# lcd13264-shield.net
KiCad netlist of a schematic drawn in EAGLE
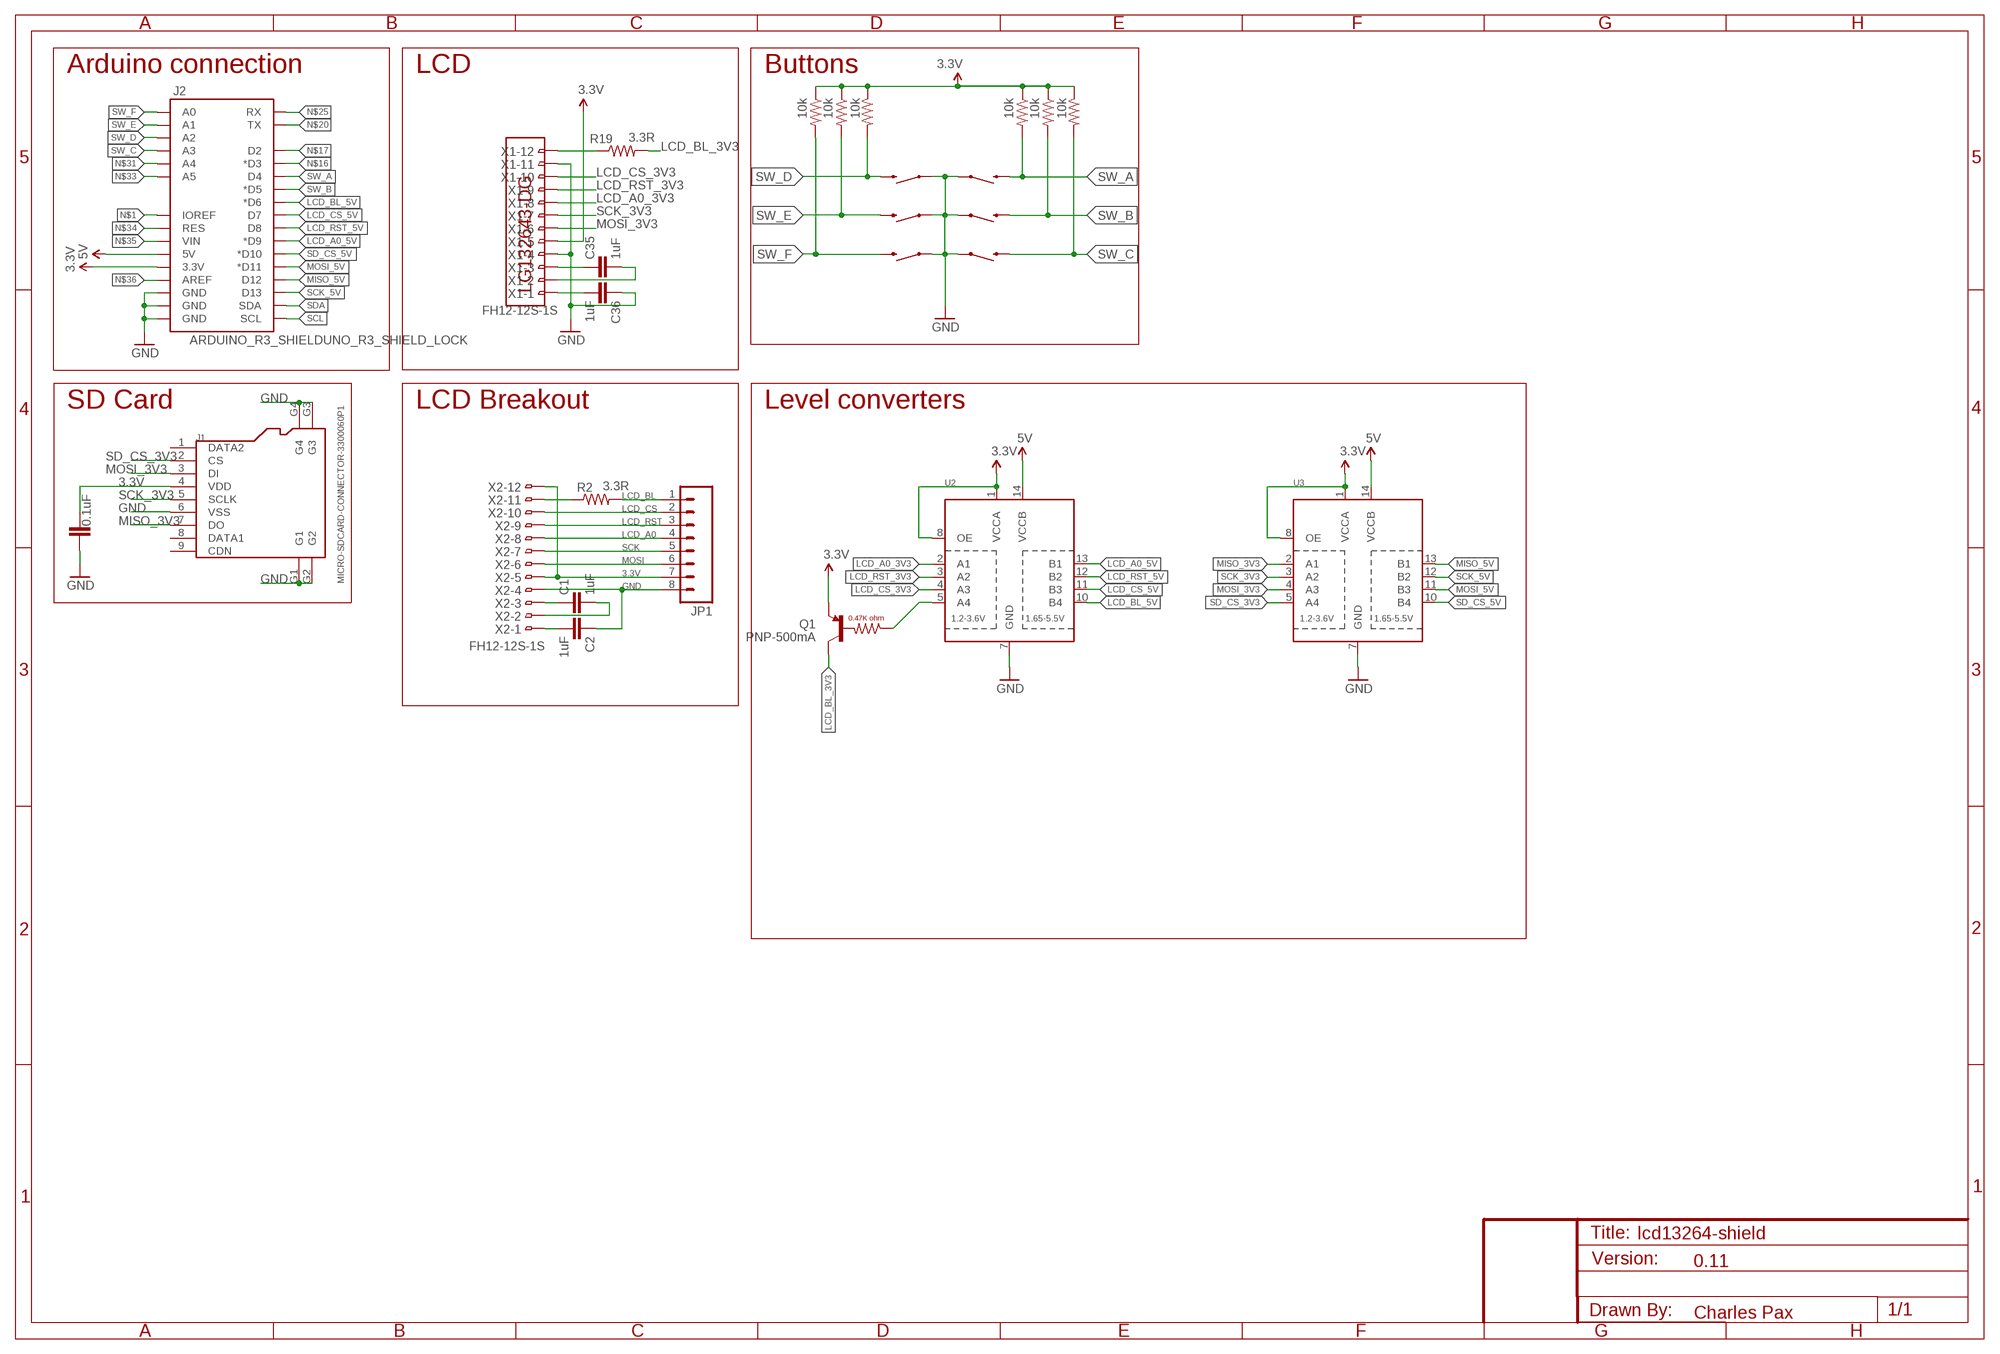
[diagram p0: schematic, sheet 1]

(export (version "E")
  (design (tool "Eeschema 10.0.6"))
  (components
    (comp (ref "C1")
      (value "1uF")
      (footprint "eagle-import:SPARKFUN-CAPACITORS_0603-CAP")
      (fields (field (name "MPN") "LMK107B7105KA-T"))
      (libsource (lib "eagle-import") (part "SPARKFUN-CAPACITORS_CAP0603-CAP"))
    )
    (comp (ref "C2")
      (value "1uF")
      (footprint "eagle-import:SPARKFUN-CAPACITORS_0603-CAP")
      (fields (field (name "MPN") "LMK107B7105KA-T"))
      (libsource (lib "eagle-import") (part "SPARKFUN-CAPACITORS_CAP0603-CAP"))
    )
    (comp (ref "C21")
      (value "0.1uF")
      (footprint "eagle-import:SPARKFUN-CAPACITORS_0603-CAP")
      (fields (field (name "MPN") "CL10B104KO8NNNC"))
      (libsource (lib "eagle-import") (part "SPARKFUN-CAPACITORS_CAP0603-CAP"))
    )
    (comp (ref "C35")
      (value "1uF")
      (footprint "eagle-import:SPARKFUN-CAPACITORS_0603-CAP")
      (fields (field (name "MPN") "LMK107B7105KA-T"))
      (libsource (lib "eagle-import") (part "SPARKFUN-CAPACITORS_CAP0603-CAP"))
    )
    (comp (ref "C36")
      (value "1uF")
      (footprint "eagle-import:SPARKFUN-CAPACITORS_0603-CAP")
      (fields (field (name "MPN") "LMK107B7105KA-T"))
      (libsource (lib "eagle-import") (part "SPARKFUN-CAPACITORS_CAP0603-CAP"))
    )
    (comp (ref "J1")
      (value "MICRO-SDCARD-CONNECTOR-3300060P1")
      (footprint "eagle-import:9P-SMD-W-RING")
      (libsource (lib "eagle-import") (part "MICRO-SDCARD-CONNECTOR-3300060P1"))
    )
    (comp (ref "J2")
      (value "ARDUINO_R3_SHIELDUNO_R3_SHIELD_LOCK")
      (footprint "eagle-import:UNO_R3_SHIELD_LOCK")
      (libsource (lib "eagle-import") (part "ARDUINO_R3_SHIELDUNO_R3_SHIELD_LOCK"))
    )
    (comp (ref "JP1")
      (value "M08")
      (footprint "eagle-import:1X08_ROUND")
      (libsource (lib "eagle-import") (part "M08"))
    )
    (comp (ref "Q1")
      (value "PNP-500mA")
      (footprint "eagle-import:SOT23-3")
      (libsource (lib "eagle-import") (part "TRANSISTOR-PNP-DDTB142TC"))
    )
    (comp (ref "R1")
      (value "10k")
      (footprint "eagle-import:SPARKFUN-RESISTORS_0603-RES")
      (fields (field (name "MPN") "RC1608J103CS"))
      (libsource (lib "eagle-import") (part "SPARKFUN-RESISTORS_RESISTOR0603-RES"))
    )
    (comp (ref "R2")
      (value "3.3R")
      (footprint "eagle-import:SPARKFUN-RESISTORS_0603-RES")
      (libsource (lib "eagle-import") (part "SPARKFUN-RESISTORS_RESISTOR0603-RES"))
    )
    (comp (ref "R8")
      (value "10k")
      (footprint "eagle-import:SPARKFUN-RESISTORS_0603-RES")
      (fields (field (name "MPN") "RC1608J103CS"))
      (libsource (lib "eagle-import") (part "SPARKFUN-RESISTORS_RESISTOR0603-RES"))
    )
    (comp (ref "R11")
      (value "10k")
      (footprint "eagle-import:SPARKFUN-RESISTORS_0603-RES")
      (fields (field (name "MPN") "RC1608J103CS"))
      (libsource (lib "eagle-import") (part "SPARKFUN-RESISTORS_RESISTOR0603-RES"))
    )
    (comp (ref "R12")
      (value "10k")
      (footprint "eagle-import:SPARKFUN-RESISTORS_0603-RES")
      (fields (field (name "MPN") "RC1608J103CS"))
      (libsource (lib "eagle-import") (part "SPARKFUN-RESISTORS_RESISTOR0603-RES"))
    )
    (comp (ref "R15")
      (value "10k")
      (footprint "eagle-import:SPARKFUN-RESISTORS_0603-RES")
      (fields (field (name "MPN") "RC1608J103CS"))
      (libsource (lib "eagle-import") (part "SPARKFUN-RESISTORS_RESISTOR0603-RES"))
    )
    (comp (ref "R16")
      (value "10k")
      (footprint "eagle-import:SPARKFUN-RESISTORS_0603-RES")
      (fields (field (name "MPN") "RC1608J103CS"))
      (libsource (lib "eagle-import") (part "SPARKFUN-RESISTORS_RESISTOR0603-RES"))
    )
    (comp (ref "R19")
      (value "3.3R")
      (footprint "eagle-import:SPARKFUN-RESISTORS_0603-RES")
      (libsource (lib "eagle-import") (part "SPARKFUN-RESISTORS_RESISTOR0603-RES"))
    )
    (comp (ref "S1")
      (value "SWITCH-MOMENTARY-2SMD")
      (footprint "eagle-import:TACTILE_SWITCH_SMD")
      (libsource (lib "eagle-import") (part "SWITCH-MOMENTARY-2SMD"))
    )
    (comp (ref "S2")
      (value "SWITCH-MOMENTARY-2SMD")
      (footprint "eagle-import:TACTILE_SWITCH_SMD")
      (libsource (lib "eagle-import") (part "SWITCH-MOMENTARY-2SMD"))
    )
    (comp (ref "S3")
      (value "SWITCH-MOMENTARY-2SMD")
      (footprint "eagle-import:TACTILE_SWITCH_SMD")
      (libsource (lib "eagle-import") (part "SWITCH-MOMENTARY-2SMD"))
    )
    (comp (ref "S4")
      (value "SWITCH-MOMENTARY-2SMD")
      (footprint "eagle-import:TACTILE_SWITCH_SMD")
      (libsource (lib "eagle-import") (part "SWITCH-MOMENTARY-2SMD"))
    )
    (comp (ref "S5")
      (value "SWITCH-MOMENTARY-2SMD")
      (footprint "eagle-import:TACTILE_SWITCH_SMD")
      (libsource (lib "eagle-import") (part "SWITCH-MOMENTARY-2SMD"))
    )
    (comp (ref "S6")
      (value "SWITCH-MOMENTARY-2SMD")
      (footprint "eagle-import:TACTILE_SWITCH_SMD")
      (libsource (lib "eagle-import") (part "SWITCH-MOMENTARY-2SMD"))
    )
    (comp (ref "U$5")
      (value "LG132643-DG")
      (footprint "eagle-import:LG132643-DG")
      (fields (field (name "MPN") "LG132643-DW"))
      (libsource (lib "eagle-import") (part "LG132643-DG"))
    )
    (comp (ref "U2")
      (value "TXB0104PWRSOIC14")
      (footprint "eagle-import:SO14")
      (libsource (lib "eagle-import") (part "TXB0104PWRSOIC14"))
    )
    (comp (ref "U3")
      (value "TXB0104PWRSOIC14")
      (footprint "eagle-import:SO14")
      (libsource (lib "eagle-import") (part "TXB0104PWRSOIC14"))
    )
    (comp (ref "X1")
      (value "FH12-12S-1S")
      (footprint "eagle-import:FH12-12S-1SH")
      (libsource (lib "eagle-import") (part "FH12-12S-1S"))
    )
    (comp (ref "X2")
      (value "FH12-12S-1S")
      (footprint "eagle-import:FH12-12S-1SH")
      (libsource (lib "eagle-import") (part "FH12-12S-1S"))
    )
  )
  (nets
    (net (code "1") (name "3.3V") (class "Default")
      (node (ref "C21") (pin "2") (pinfunction "2_2") (pintype "passive"))
      (node (ref "J1") (pin "4") (pinfunction "VDD_4") (pintype "bidirectional"))
      (node (ref "J2") (pin "3.3V") (pinfunction "3.3V_3.3V") (pintype "bidirectional"))
      (node (ref "Q1") (pin "2") (pinfunction "E_2") (pintype "passive"))
      (node (ref "R1") (pin "1") (pinfunction "1_1") (pintype "passive"))
      (node (ref "R11") (pin "1") (pinfunction "1_1") (pintype "passive"))
      (node (ref "R12") (pin "1") (pinfunction "1_1") (pintype "passive"))
      (node (ref "R15") (pin "1") (pinfunction "1_1") (pintype "passive"))
      (node (ref "R16") (pin "1") (pinfunction "1_1") (pintype "passive"))
      (node (ref "R8") (pin "1") (pinfunction "1_1") (pintype "passive"))
      (node (ref "U2") (pin "1") (pinfunction "VCCA_1") (pintype "bidirectional"))
      (node (ref "U2") (pin "8") (pinfunction "OE_8") (pintype "bidirectional"))
      (node (ref "U3") (pin "1") (pinfunction "VCCA_1") (pintype "bidirectional"))
      (node (ref "U3") (pin "8") (pinfunction "OE_8") (pintype "bidirectional"))
      (node (ref "X1") (pin "5") (pinfunction "1_5") (pintype "passive"))
    )
    (net (code "2") (name "5V") (class "Default")
      (node (ref "J2") (pin "5V") (pinfunction "5V_5V") (pintype "bidirectional"))
      (node (ref "U2") (pin "14") (pinfunction "VCCB_14") (pintype "bidirectional"))
      (node (ref "U3") (pin "14") (pinfunction "VCCB_14") (pintype "bidirectional"))
    )
    (net (code "3") (name "GND") (class "Default")
      (node (ref "C21") (pin "1") (pinfunction "1_1") (pintype "passive"))
      (node (ref "C36") (pin "1") (pinfunction "1_1") (pintype "passive"))
      (node (ref "J1") (pin "6") (pinfunction "VSS_6") (pintype "bidirectional"))
      (node (ref "J1") (pin "G1") (pinfunction "G1_G1") (pintype "bidirectional"))
      (node (ref "J1") (pin "G2") (pinfunction "G2_G2") (pintype "bidirectional"))
      (node (ref "J1") (pin "G3") (pinfunction "G3_G3") (pintype "bidirectional"))
      (node (ref "J1") (pin "G4") (pinfunction "G4_G4") (pintype "bidirectional"))
      (node (ref "J2") (pin "GND@0") (pinfunction "GND_GND@0") (pintype "bidirectional"))
      (node (ref "J2") (pin "GND@1") (pinfunction "GND_GND@1") (pintype "bidirectional"))
      (node (ref "J2") (pin "GND@2") (pinfunction "GND_GND@2") (pintype "bidirectional"))
      (node (ref "S1") (pin "1") (pinfunction "1_1") (pintype "passive"))
      (node (ref "S2") (pin "1") (pinfunction "1_1") (pintype "passive"))
      (node (ref "S3") (pin "1") (pinfunction "1_1") (pintype "passive"))
      (node (ref "S4") (pin "1") (pinfunction "1_1") (pintype "passive"))
      (node (ref "S5") (pin "1") (pinfunction "1_1") (pintype "passive"))
      (node (ref "S6") (pin "1") (pinfunction "1_1") (pintype "passive"))
      (node (ref "U2") (pin "7") (pinfunction "GND_7") (pintype "bidirectional"))
      (node (ref "U3") (pin "7") (pinfunction "GND_7") (pintype "bidirectional"))
      (node (ref "X1") (pin "11") (pinfunction "1_11") (pintype "passive"))
      (node (ref "X1") (pin "4") (pinfunction "1_4") (pintype "passive"))
    )
    (net (code "4") (name "LCD_A0_3V3") (class "Default")
      (node (ref "U2") (pin "2") (pinfunction "A1_2") (pintype "bidirectional"))
      (node (ref "X1") (pin "8") (pinfunction "1_8") (pintype "passive"))
    )
    (net (code "5") (name "LCD_A0_5V") (class "Default")
      (node (ref "J2") (pin "D9") (pinfunction "*D9_D9") (pintype "bidirectional"))
      (node (ref "U2") (pin "13") (pinfunction "B1_13") (pintype "bidirectional"))
    )
    (net (code "6") (name "LCD_BL_3V3") (class "Default")
      (node (ref "Q1") (pin "3") (pinfunction "C_3") (pintype "passive"))
      (node (ref "R19") (pin "2") (pinfunction "2_2") (pintype "passive"))
    )
    (net (code "7") (name "LCD_BL_5V") (class "Default")
      (node (ref "J2") (pin "D6") (pinfunction "*D6_D6") (pintype "bidirectional"))
      (node (ref "U2") (pin "10") (pinfunction "B4_10") (pintype "bidirectional"))
    )
    (net (code "8") (name "LCD_CS_3V3") (class "Default")
      (node (ref "U2") (pin "4") (pinfunction "A3_4") (pintype "bidirectional"))
      (node (ref "X1") (pin "10") (pinfunction "1_10") (pintype "passive"))
    )
    (net (code "9") (name "LCD_CS_5V") (class "Default")
      (node (ref "J2") (pin "D7") (pinfunction "D7_D7") (pintype "bidirectional"))
      (node (ref "U2") (pin "11") (pinfunction "B3_11") (pintype "bidirectional"))
    )
    (net (code "10") (name "LCD_RST_3V3") (class "Default")
      (node (ref "U2") (pin "3") (pinfunction "A2_3") (pintype "bidirectional"))
      (node (ref "X1") (pin "9") (pinfunction "1_9") (pintype "passive"))
    )
    (net (code "11") (name "LCD_RST_5V") (class "Default")
      (node (ref "J2") (pin "D8") (pinfunction "D8_D8") (pintype "bidirectional"))
      (node (ref "U2") (pin "12") (pinfunction "B2_12") (pintype "bidirectional"))
    )
    (net (code "12") (name "MISO_3V3") (class "Default")
      (node (ref "J1") (pin "7") (pinfunction "DO_7") (pintype "bidirectional"))
      (node (ref "U3") (pin "2") (pinfunction "A1_2") (pintype "bidirectional"))
    )
    (net (code "13") (name "MISO_5V") (class "Default")
      (node (ref "J2") (pin "D12") (pinfunction "D12_D12") (pintype "bidirectional"))
      (node (ref "U3") (pin "13") (pinfunction "B1_13") (pintype "bidirectional"))
    )
    (net (code "14") (name "MOSI_3V3") (class "Default")
      (node (ref "J1") (pin "3") (pinfunction "DI_3") (pintype "bidirectional"))
      (node (ref "U3") (pin "4") (pinfunction "A3_4") (pintype "bidirectional"))
      (node (ref "X1") (pin "6") (pinfunction "1_6") (pintype "passive"))
    )
    (net (code "15") (name "MOSI_5V") (class "Default")
      (node (ref "J2") (pin "D11") (pinfunction "*D11_D11") (pintype "bidirectional"))
      (node (ref "U3") (pin "11") (pinfunction "B3_11") (pintype "bidirectional"))
    )
    (net (code "16") (name "N$1") (class "Default")
      (node (ref "J2") (pin "IOREF") (pinfunction "IOREF_IOREF") (pintype "bidirectional"))
    )
    (net (code "17") (name "N$16") (class "Default")
      (node (ref "J2") (pin "D3") (pinfunction "*D3_D3") (pintype "bidirectional"))
    )
    (net (code "18") (name "N$17") (class "Default")
      (node (ref "J2") (pin "D2") (pinfunction "D2_D2") (pintype "bidirectional"))
    )
    (net (code "19") (name "N$20") (class "Default")
      (node (ref "J2") (pin "TX") (pinfunction "TX_TX") (pintype "bidirectional"))
    )
    (net (code "20") (name "N$25") (class "Default")
      (node (ref "J2") (pin "RX") (pinfunction "RX_RX") (pintype "bidirectional"))
    )
    (net (code "21") (name "N$31") (class "Default")
      (node (ref "J2") (pin "A4") (pinfunction "A4_A4") (pintype "bidirectional"))
    )
    (net (code "22") (name "N$33") (class "Default")
      (node (ref "J2") (pin "A5") (pinfunction "A5_A5") (pintype "bidirectional"))
    )
    (net (code "23") (name "N$34") (class "Default")
      (node (ref "J2") (pin "RES") (pinfunction "RES_RES") (pintype "bidirectional"))
    )
    (net (code "24") (name "N$35") (class "Default")
      (node (ref "J2") (pin "VIN") (pinfunction "VIN_VIN") (pintype "bidirectional"))
    )
    (net (code "25") (name "N$36") (class "Default")
      (node (ref "J2") (pin "AREF") (pinfunction "AREF_AREF") (pintype "bidirectional"))
    )
    (net (code "26") (name "Net-(C2-Pad2)") (class "Default")
      (node (ref "C2") (pin "2") (pinfunction "2_2") (pintype "passive"))
      (node (ref "X2") (pin "1") (pinfunction "1_1") (pintype "passive"))
    )
    (net (code "27") (name "Net-(C36-Pad2)") (class "Default")
      (node (ref "C36") (pin "2") (pinfunction "2_2") (pintype "passive"))
      (node (ref "X1") (pin "1") (pinfunction "1_1") (pintype "passive"))
    )
    (net (code "28") (name "Net-(JP1-Pad1)") (class "Default")
      (node (ref "JP1") (pin "1") (pinfunction "1_1") (pintype "passive"))
      (node (ref "R2") (pin "2") (pinfunction "2_2") (pintype "passive"))
    )
    (net (code "29") (name "Net-(Q1-B)") (class "Default")
      (node (ref "Q1") (pin "1") (pinfunction "B_1") (pintype "passive"))
      (node (ref "U2") (pin "5") (pinfunction "A4_5") (pintype "bidirectional"))
    )
    (net (code "30") (name "Net-(X1D-1)") (class "Default")
      (node (ref "R19") (pin "1") (pinfunction "1_1") (pintype "passive"))
      (node (ref "X1") (pin "12") (pinfunction "1_12") (pintype "passive"))
    )
    (net (code "31") (name "Net-(X1E-1)") (class "Default")
      (node (ref "C35") (pin "2") (pinfunction "2_2") (pintype "passive"))
      (node (ref "X1") (pin "2") (pinfunction "1_2") (pintype "passive"))
    )
    (net (code "32") (name "Net-(X1F-1)") (class "Default")
      (node (ref "C35") (pin "1") (pinfunction "1_1") (pintype "passive"))
      (node (ref "X1") (pin "3") (pinfunction "1_3") (pintype "passive"))
    )
    (net (code "33") (name "Net-(X2B-1)") (class "Default")
      (node (ref "JP1") (pin "2") (pinfunction "2_2") (pintype "passive"))
      (node (ref "X2") (pin "10") (pinfunction "1_10") (pintype "passive"))
    )
    (net (code "34") (name "Net-(X2C-1)") (class "Default")
      (node (ref "R2") (pin "1") (pinfunction "1_1") (pintype "passive"))
      (node (ref "X2") (pin "11") (pinfunction "1_11") (pintype "passive"))
    )
    (net (code "35") (name "Net-(X2D-1)") (class "Default")
      (node (ref "JP1") (pin "7") (pinfunction "7_7") (pintype "passive"))
      (node (ref "X2") (pin "12") (pinfunction "1_12") (pintype "passive"))
      (node (ref "X2") (pin "5") (pinfunction "1_5") (pintype "passive"))
    )
    (net (code "36") (name "Net-(X2E-1)") (class "Default")
      (node (ref "C1") (pin "2") (pinfunction "2_2") (pintype "passive"))
      (node (ref "X2") (pin "2") (pinfunction "1_2") (pintype "passive"))
    )
    (net (code "37") (name "Net-(X2F-1)") (class "Default")
      (node (ref "C1") (pin "1") (pinfunction "1_1") (pintype "passive"))
      (node (ref "X2") (pin "3") (pinfunction "1_3") (pintype "passive"))
    )
    (net (code "38") (name "Net-(X2G-1)") (class "Default")
      (node (ref "C2") (pin "1") (pinfunction "1_1") (pintype "passive"))
      (node (ref "JP1") (pin "8") (pinfunction "8_8") (pintype "passive"))
      (node (ref "X2") (pin "4") (pinfunction "1_4") (pintype "passive"))
    )
    (net (code "39") (name "Net-(X2I-1)") (class "Default")
      (node (ref "JP1") (pin "6") (pinfunction "6_6") (pintype "passive"))
      (node (ref "X2") (pin "6") (pinfunction "1_6") (pintype "passive"))
    )
    (net (code "40") (name "Net-(X2J-1)") (class "Default")
      (node (ref "JP1") (pin "5") (pinfunction "5_5") (pintype "passive"))
      (node (ref "X2") (pin "7") (pinfunction "1_7") (pintype "passive"))
    )
    (net (code "41") (name "Net-(X2K-1)") (class "Default")
      (node (ref "JP1") (pin "4") (pinfunction "4_4") (pintype "passive"))
      (node (ref "X2") (pin "8") (pinfunction "1_8") (pintype "passive"))
    )
    (net (code "42") (name "Net-(X2L-1)") (class "Default")
      (node (ref "JP1") (pin "3") (pinfunction "3_3") (pintype "passive"))
      (node (ref "X2") (pin "9") (pinfunction "1_9") (pintype "passive"))
    )
    (net (code "43") (name "SCK_3V3") (class "Default")
      (node (ref "J1") (pin "5") (pinfunction "SCLK_5") (pintype "bidirectional"))
      (node (ref "U3") (pin "3") (pinfunction "A2_3") (pintype "bidirectional"))
      (node (ref "X1") (pin "7") (pinfunction "1_7") (pintype "passive"))
    )
    (net (code "44") (name "SCK_5V") (class "Default")
      (node (ref "J2") (pin "D13") (pinfunction "D13_D13") (pintype "bidirectional"))
      (node (ref "U3") (pin "12") (pinfunction "B2_12") (pintype "bidirectional"))
    )
    (net (code "45") (name "SCL") (class "Default")
      (node (ref "J2") (pin "SCL") (pinfunction "SCL_SCL") (pintype "bidirectional"))
    )
    (net (code "46") (name "SDA") (class "Default")
      (node (ref "J2") (pin "SDA") (pinfunction "SDA_SDA") (pintype "bidirectional"))
    )
    (net (code "47") (name "SD_CS_3V3") (class "Default")
      (node (ref "J1") (pin "2") (pinfunction "CS_2") (pintype "bidirectional"))
      (node (ref "U3") (pin "5") (pinfunction "A4_5") (pintype "bidirectional"))
    )
    (net (code "48") (name "SD_CS_5V") (class "Default")
      (node (ref "J2") (pin "D10") (pinfunction "*D10_D10") (pintype "bidirectional"))
      (node (ref "U3") (pin "10") (pinfunction "B4_10") (pintype "bidirectional"))
    )
    (net (code "49") (name "SW_A") (class "Default")
      (node (ref "J2") (pin "D4") (pinfunction "D4_D4") (pintype "bidirectional"))
      (node (ref "R8") (pin "2") (pinfunction "2_2") (pintype "passive"))
      (node (ref "S3") (pin "3") (pinfunction "2_3") (pintype "passive"))
    )
    (net (code "50") (name "SW_B") (class "Default")
      (node (ref "J2") (pin "D5") (pinfunction "*D5_D5") (pintype "bidirectional"))
      (node (ref "R11") (pin "2") (pinfunction "2_2") (pintype "passive"))
      (node (ref "S2") (pin "3") (pinfunction "2_3") (pintype "passive"))
    )
    (net (code "51") (name "SW_C") (class "Default")
      (node (ref "J2") (pin "A3") (pinfunction "A3_A3") (pintype "bidirectional"))
      (node (ref "R12") (pin "2") (pinfunction "2_2") (pintype "passive"))
      (node (ref "S1") (pin "3") (pinfunction "2_3") (pintype "passive"))
    )
    (net (code "52") (name "SW_D") (class "Default")
      (node (ref "J2") (pin "A2") (pinfunction "A2_A2") (pintype "bidirectional"))
      (node (ref "R15") (pin "2") (pinfunction "2_2") (pintype "passive"))
      (node (ref "S4") (pin "3") (pinfunction "2_3") (pintype "passive"))
    )
    (net (code "53") (name "SW_E") (class "Default")
      (node (ref "J2") (pin "A1") (pinfunction "A1_A1") (pintype "bidirectional"))
      (node (ref "R16") (pin "2") (pinfunction "2_2") (pintype "passive"))
      (node (ref "S5") (pin "3") (pinfunction "2_3") (pintype "passive"))
    )
    (net (code "54") (name "SW_F") (class "Default")
      (node (ref "J2") (pin "A0") (pinfunction "A0_A0") (pintype "bidirectional"))
      (node (ref "R1") (pin "2") (pinfunction "2_2") (pintype "passive"))
      (node (ref "S6") (pin "3") (pinfunction "2_3") (pintype "passive"))
    )
    (net (code "55") (name "unconnected-(J1-CDN-Pad9)") (class "Default")
      (node (ref "J1") (pin "9") (pinfunction "CDN_9") (pintype "bidirectional"))
    )
    (net (code "56") (name "unconnected-(J1-DATA1-Pad8)") (class "Default")
      (node (ref "J1") (pin "8") (pinfunction "DATA1_8") (pintype "bidirectional"))
    )
    (net (code "57") (name "unconnected-(J1-DATA2-Pad1)") (class "Default")
      (node (ref "J1") (pin "1") (pinfunction "DATA2_1") (pintype "bidirectional"))
    )
  )
)
